# MUX_CHANNEL.net
KiCad netlist of a schematic drawn in Altium Designer
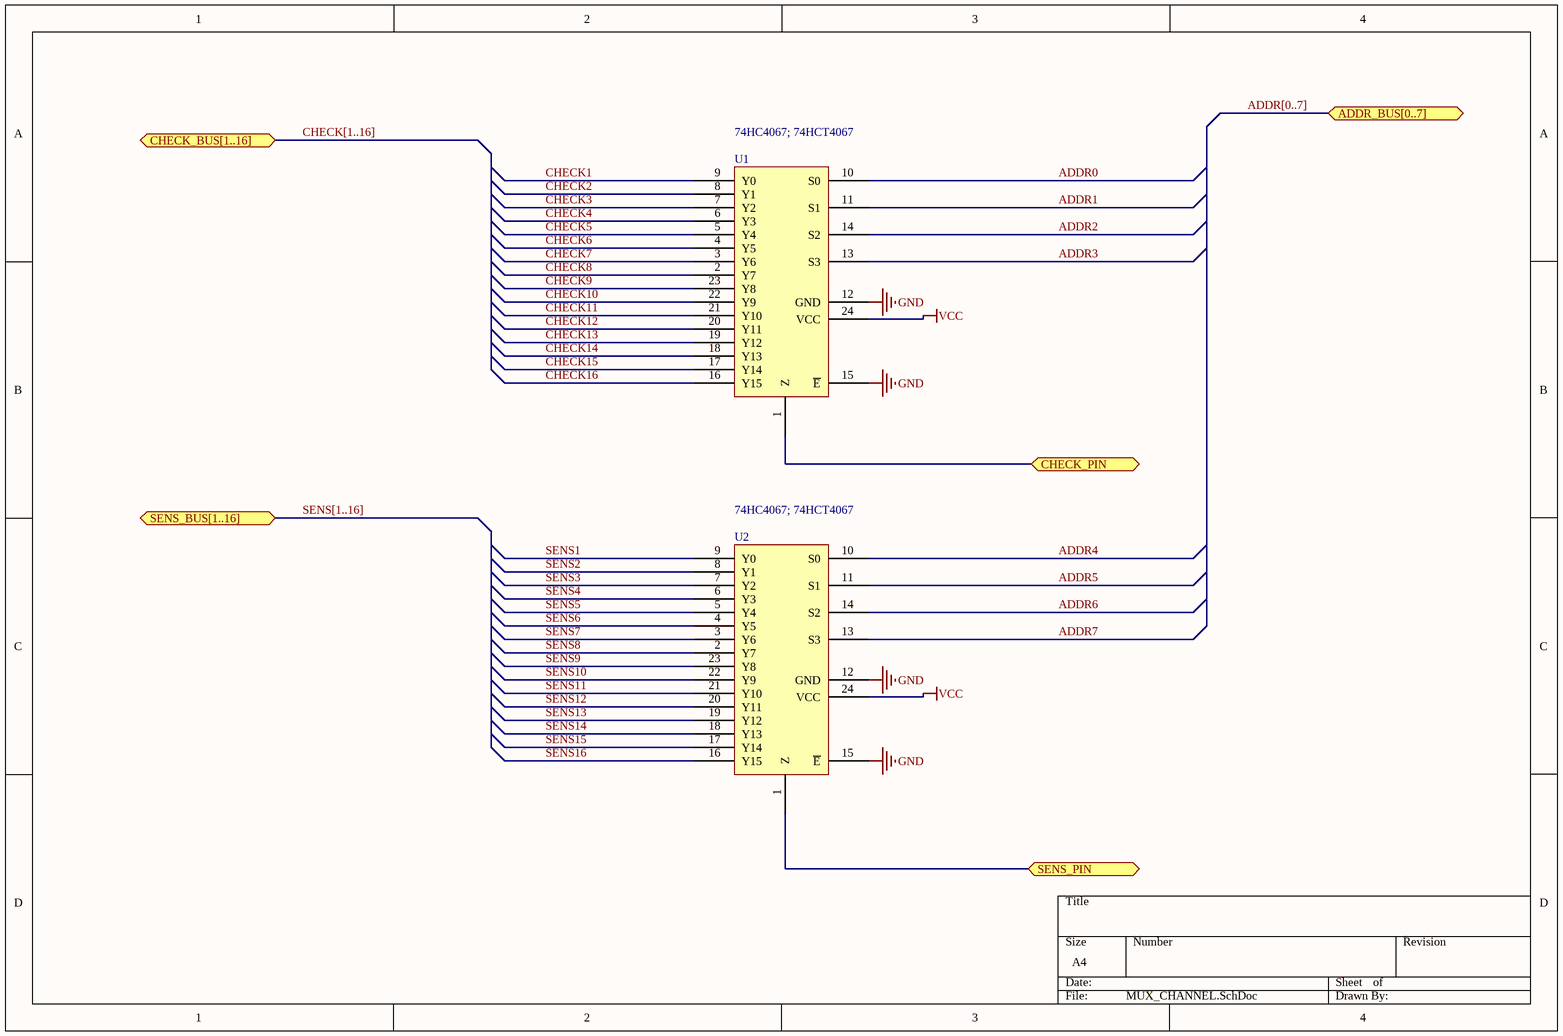
[diagram p0: MUX_CHANNEL.SchDoc]

(export (version "E")
  (design (tool "Eeschema 10.0.6"))
  (components
    (comp (ref "U1")
      (value "74HC4067; 74HCT4067")
      (footprint "SO24")
      (description "16-channel analog multiplexer/demultiplexer")
      (libsource (lib "Common Devices") (part "74HC4067; 74HCT4067"))
    )
    (comp (ref "U2")
      (value "74HC4067; 74HCT4067")
      (footprint "SO24")
      (description "16-channel analog multiplexer/demultiplexer")
      (libsource (lib "Common Devices") (part "74HC4067; 74HCT4067"))
    )
  )
  (nets
    (net (code "1") (name "/ADDR0") (class "Default")
      (node (ref "U1") (pin "10") (pinfunction "S0_10") (pintype "passive"))
    )
    (net (code "2") (name "/ADDR1") (class "Default")
      (node (ref "U1") (pin "11") (pinfunction "S1_11") (pintype "passive"))
    )
    (net (code "3") (name "/ADDR2") (class "Default")
      (node (ref "U1") (pin "14") (pinfunction "S2_14") (pintype "passive"))
    )
    (net (code "4") (name "/ADDR3") (class "Default")
      (node (ref "U1") (pin "13") (pinfunction "S3_13") (pintype "passive"))
    )
    (net (code "5") (name "/ADDR4") (class "Default")
      (node (ref "U2") (pin "10") (pinfunction "S0_10") (pintype "passive"))
    )
    (net (code "6") (name "/ADDR5") (class "Default")
      (node (ref "U2") (pin "11") (pinfunction "S1_11") (pintype "passive"))
    )
    (net (code "7") (name "/ADDR6") (class "Default")
      (node (ref "U2") (pin "14") (pinfunction "S2_14") (pintype "passive"))
    )
    (net (code "8") (name "/ADDR7") (class "Default")
      (node (ref "U2") (pin "13") (pinfunction "S3_13") (pintype "passive"))
    )
    (net (code "10") (name "/CHECK1") (class "Default")
      (node (ref "U1") (pin "9") (pinfunction "Y0_9") (pintype "passive"))
    )
    (net (code "11") (name "/CHECK2") (class "Default")
      (node (ref "U1") (pin "8") (pinfunction "Y1_8") (pintype "passive"))
    )
    (net (code "12") (name "/CHECK3") (class "Default")
      (node (ref "U1") (pin "7") (pinfunction "Y2_7") (pintype "passive"))
    )
    (net (code "13") (name "/CHECK4") (class "Default")
      (node (ref "U1") (pin "6") (pinfunction "Y3_6") (pintype "passive"))
    )
    (net (code "14") (name "/CHECK5") (class "Default")
      (node (ref "U1") (pin "5") (pinfunction "Y4_5") (pintype "passive"))
    )
    (net (code "15") (name "/CHECK6") (class "Default")
      (node (ref "U1") (pin "4") (pinfunction "Y5_4") (pintype "passive"))
    )
    (net (code "16") (name "/CHECK7") (class "Default")
      (node (ref "U1") (pin "3") (pinfunction "Y6_3") (pintype "passive"))
    )
    (net (code "17") (name "/CHECK8") (class "Default")
      (node (ref "U1") (pin "2") (pinfunction "Y7_2") (pintype "passive"))
    )
    (net (code "18") (name "/CHECK9") (class "Default")
      (node (ref "U1") (pin "23") (pinfunction "Y8_23") (pintype "passive"))
    )
    (net (code "19") (name "/CHECK10") (class "Default")
      (node (ref "U1") (pin "22") (pinfunction "Y9_22") (pintype "passive"))
    )
    (net (code "20") (name "/CHECK11") (class "Default")
      (node (ref "U1") (pin "21") (pinfunction "Y10_21") (pintype "passive"))
    )
    (net (code "21") (name "/CHECK12") (class "Default")
      (node (ref "U1") (pin "20") (pinfunction "Y11_20") (pintype "passive"))
    )
    (net (code "22") (name "/CHECK13") (class "Default")
      (node (ref "U1") (pin "19") (pinfunction "Y12_19") (pintype "passive"))
    )
    (net (code "23") (name "/CHECK14") (class "Default")
      (node (ref "U1") (pin "18") (pinfunction "Y13_18") (pintype "passive"))
    )
    (net (code "24") (name "/CHECK15") (class "Default")
      (node (ref "U1") (pin "17") (pinfunction "Y14_17") (pintype "passive"))
    )
    (net (code "25") (name "/CHECK16") (class "Default")
      (node (ref "U1") (pin "16") (pinfunction "Y15_16") (pintype "passive"))
    )
    (net (code "27") (name "/CHECK_PIN") (class "Default")
      (node (ref "U1") (pin "1") (pinfunction "Z_1") (pintype "passive"))
    )
    (net (code "28") (name "/SENS1") (class "Default")
      (node (ref "U2") (pin "9") (pinfunction "Y0_9") (pintype "passive"))
    )
    (net (code "29") (name "/SENS2") (class "Default")
      (node (ref "U2") (pin "8") (pinfunction "Y1_8") (pintype "passive"))
    )
    (net (code "30") (name "/SENS3") (class "Default")
      (node (ref "U2") (pin "7") (pinfunction "Y2_7") (pintype "passive"))
    )
    (net (code "31") (name "/SENS4") (class "Default")
      (node (ref "U2") (pin "6") (pinfunction "Y3_6") (pintype "passive"))
    )
    (net (code "32") (name "/SENS5") (class "Default")
      (node (ref "U2") (pin "5") (pinfunction "Y4_5") (pintype "passive"))
    )
    (net (code "33") (name "/SENS6") (class "Default")
      (node (ref "U2") (pin "4") (pinfunction "Y5_4") (pintype "passive"))
    )
    (net (code "34") (name "/SENS7") (class "Default")
      (node (ref "U2") (pin "3") (pinfunction "Y6_3") (pintype "passive"))
    )
    (net (code "35") (name "/SENS8") (class "Default")
      (node (ref "U2") (pin "2") (pinfunction "Y7_2") (pintype "passive"))
    )
    (net (code "36") (name "/SENS9") (class "Default")
      (node (ref "U2") (pin "23") (pinfunction "Y8_23") (pintype "passive"))
    )
    (net (code "37") (name "/SENS10") (class "Default")
      (node (ref "U2") (pin "22") (pinfunction "Y9_22") (pintype "passive"))
    )
    (net (code "38") (name "/SENS11") (class "Default")
      (node (ref "U2") (pin "21") (pinfunction "Y10_21") (pintype "passive"))
    )
    (net (code "39") (name "/SENS12") (class "Default")
      (node (ref "U2") (pin "20") (pinfunction "Y11_20") (pintype "passive"))
    )
    (net (code "40") (name "/SENS13") (class "Default")
      (node (ref "U2") (pin "19") (pinfunction "Y12_19") (pintype "passive"))
    )
    (net (code "41") (name "/SENS14") (class "Default")
      (node (ref "U2") (pin "18") (pinfunction "Y13_18") (pintype "passive"))
    )
    (net (code "42") (name "/SENS15") (class "Default")
      (node (ref "U2") (pin "17") (pinfunction "Y14_17") (pintype "passive"))
    )
    (net (code "43") (name "/SENS16") (class "Default")
      (node (ref "U2") (pin "16") (pinfunction "Y15_16") (pintype "passive"))
    )
    (net (code "45") (name "/SENS_PIN") (class "Default")
      (node (ref "U2") (pin "1") (pinfunction "Z_1") (pintype "passive"))
    )
    (net (code "46") (name "GND") (class "Default")
      (node (ref "U1") (pin "12") (pinfunction "GND_12") (pintype "passive"))
      (node (ref "U1") (pin "15") (pinfunction "~{E}_15") (pintype "passive"))
      (node (ref "U2") (pin "12") (pinfunction "GND_12") (pintype "passive"))
      (node (ref "U2") (pin "15") (pinfunction "~{E}_15") (pintype "passive"))
    )
    (net (code "47") (name "VCC") (class "Default")
      (node (ref "U1") (pin "24") (pinfunction "VCC_24") (pintype "passive"))
      (node (ref "U2") (pin "24") (pinfunction "VCC_24") (pintype "passive"))
    )
  )
)
